# Stepper_driver_group.net
KiCad netlist of a schematic drawn in Altium Designer
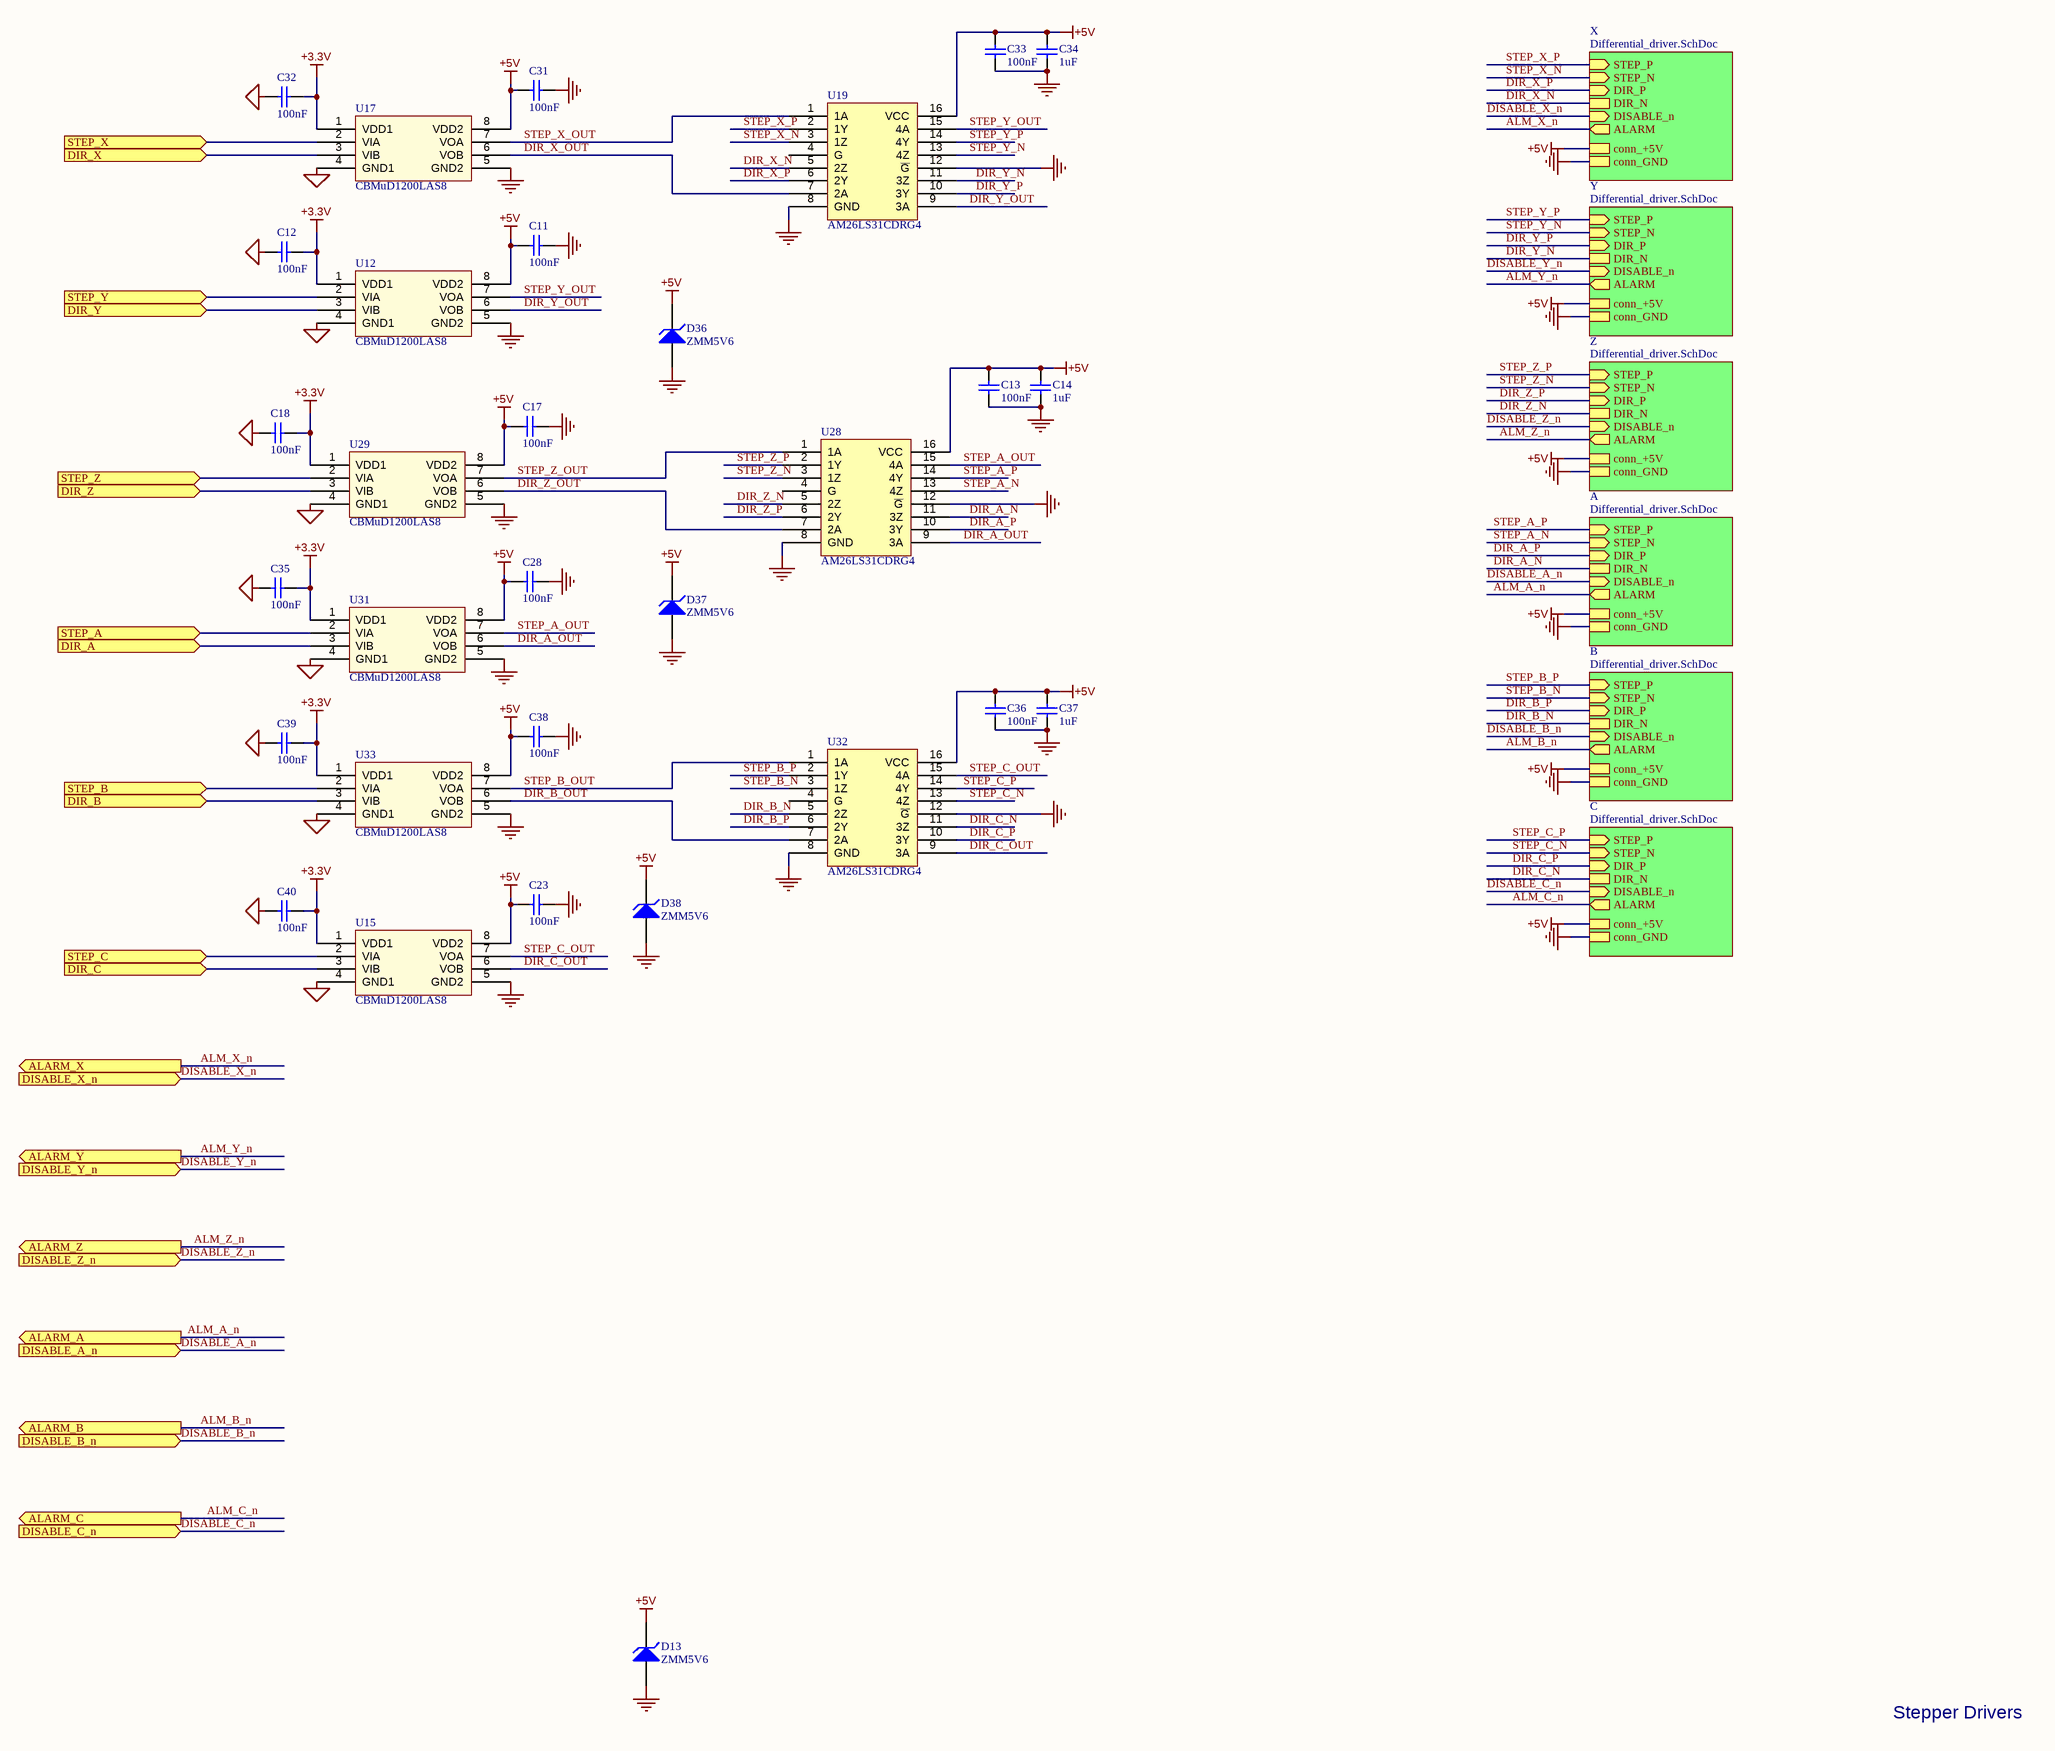
[diagram p0: Stepper_driver_group.SchDoc]

(export (version "E")
  (design (tool "Eeschema 10.0.6"))
  (components
    (comp (ref "C11")
      (value "100nF")
      (footprint "0402_C")
      (description "Chip capacitors")
      (fields
        (field (name "MANUFACTURER") "Samsung Electro-Mechanics")
        (field (name "PARTNUMBER") "CL05B104KO5NNNC")
      )
      (libsource (lib "Cap") (part "0402 100nF (104) 10% 16V"))
    )
    (comp (ref "C12")
      (value "100nF")
      (footprint "0402_C")
      (description "Chip capacitors")
      (fields
        (field (name "MANUFACTURER") "Samsung Electro-Mechanics")
        (field (name "PARTNUMBER") "CL05B104KO5NNNC")
      )
      (libsource (lib "Cap") (part "0402 100nF (104) 10% 16V"))
    )
    (comp (ref "C13")
      (value "100nF")
      (footprint "0402_C")
      (description "Chip capacitors")
      (fields
        (field (name "MANUFACTURER") "Samsung Electro-Mechanics")
        (field (name "PARTNUMBER") "CL05B104KO5NNNC")
      )
      (libsource (lib "Cap") (part "0402 100nF (104) 10% 16V"))
    )
    (comp (ref "C14")
      (value "1uF")
      (footprint "0603_C")
      (description "Chip capacitors")
      (fields
        (field (name "MANUFACTURER") "Samsung Electro-Mechanics")
        (field (name "PARTNUMBER") "CL10A105KB8NNNC")
      )
      (libsource (lib "Cap") (part "0603 1uF (105) 10% 50V"))
    )
    (comp (ref "C17")
      (value "100nF")
      (footprint "0402_C")
      (description "Chip capacitors")
      (fields
        (field (name "MANUFACTURER") "Samsung Electro-Mechanics")
        (field (name "PARTNUMBER") "CL05B104KO5NNNC")
      )
      (libsource (lib "Cap") (part "0402 100nF (104) 10% 16V"))
    )
    (comp (ref "C18")
      (value "100nF")
      (footprint "0402_C")
      (description "Chip capacitors")
      (fields
        (field (name "MANUFACTURER") "Samsung Electro-Mechanics")
        (field (name "PARTNUMBER") "CL05B104KO5NNNC")
      )
      (libsource (lib "Cap") (part "0402 100nF (104) 10% 16V"))
    )
    (comp (ref "C23")
      (value "100nF")
      (footprint "0402_C")
      (description "Chip capacitors")
      (fields
        (field (name "MANUFACTURER") "Samsung Electro-Mechanics")
        (field (name "PARTNUMBER") "CL05B104KO5NNNC")
      )
      (libsource (lib "Cap") (part "0402 100nF (104) 10% 16V"))
    )
    (comp (ref "C28")
      (value "100nF")
      (footprint "0402_C")
      (description "Chip capacitors")
      (fields
        (field (name "MANUFACTURER") "Samsung Electro-Mechanics")
        (field (name "PARTNUMBER") "CL05B104KO5NNNC")
      )
      (libsource (lib "Cap") (part "0402 100nF (104) 10% 16V"))
    )
    (comp (ref "C31")
      (value "100nF")
      (footprint "0402_C")
      (description "Chip capacitors")
      (fields
        (field (name "MANUFACTURER") "Samsung Electro-Mechanics")
        (field (name "PARTNUMBER") "CL05B104KO5NNNC")
      )
      (libsource (lib "Cap") (part "0402 100nF (104) 10% 16V"))
    )
    (comp (ref "C32")
      (value "100nF")
      (footprint "0402_C")
      (description "Chip capacitors")
      (fields
        (field (name "MANUFACTURER") "Samsung Electro-Mechanics")
        (field (name "PARTNUMBER") "CL05B104KO5NNNC")
      )
      (libsource (lib "Cap") (part "0402 100nF (104) 10% 16V"))
    )
    (comp (ref "C33")
      (value "100nF")
      (footprint "0402_C")
      (description "Chip capacitors")
      (fields
        (field (name "MANUFACTURER") "Samsung Electro-Mechanics")
        (field (name "PARTNUMBER") "CL05B104KO5NNNC")
      )
      (libsource (lib "Cap") (part "0402 100nF (104) 10% 16V"))
    )
    (comp (ref "C34")
      (value "1uF")
      (footprint "0603_C")
      (description "Chip capacitors")
      (fields
        (field (name "MANUFACTURER") "Samsung Electro-Mechanics")
        (field (name "PARTNUMBER") "CL10A105KB8NNNC")
      )
      (libsource (lib "Cap") (part "0603 1uF (105) 10% 50V"))
    )
    (comp (ref "C35")
      (value "100nF")
      (footprint "0402_C")
      (description "Chip capacitors")
      (fields
        (field (name "MANUFACTURER") "Samsung Electro-Mechanics")
        (field (name "PARTNUMBER") "CL05B104KO5NNNC")
      )
      (libsource (lib "Cap") (part "0402 100nF (104) 10% 16V"))
    )
    (comp (ref "C36")
      (value "100nF")
      (footprint "0402_C")
      (description "Chip capacitors")
      (fields
        (field (name "MANUFACTURER") "Samsung Electro-Mechanics")
        (field (name "PARTNUMBER") "CL05B104KO5NNNC")
      )
      (libsource (lib "Cap") (part "0402 100nF (104) 10% 16V"))
    )
    (comp (ref "C37")
      (value "1uF")
      (footprint "0603_C")
      (description "Chip capacitors")
      (fields
        (field (name "MANUFACTURER") "Samsung Electro-Mechanics")
        (field (name "PARTNUMBER") "CL10A105KB8NNNC")
      )
      (libsource (lib "Cap") (part "0603 1uF (105) 10% 50V"))
    )
    (comp (ref "C38")
      (value "100nF")
      (footprint "0402_C")
      (description "Chip capacitors")
      (fields
        (field (name "MANUFACTURER") "Samsung Electro-Mechanics")
        (field (name "PARTNUMBER") "CL05B104KO5NNNC")
      )
      (libsource (lib "Cap") (part "0402 100nF (104) 10% 16V"))
    )
    (comp (ref "C39")
      (value "100nF")
      (footprint "0402_C")
      (description "Chip capacitors")
      (fields
        (field (name "MANUFACTURER") "Samsung Electro-Mechanics")
        (field (name "PARTNUMBER") "CL05B104KO5NNNC")
      )
      (libsource (lib "Cap") (part "0402 100nF (104) 10% 16V"))
    )
    (comp (ref "C40")
      (value "100nF")
      (footprint "0402_C")
      (description "Chip capacitors")
      (fields
        (field (name "MANUFACTURER") "Samsung Electro-Mechanics")
        (field (name "PARTNUMBER") "CL05B104KO5NNNC")
      )
      (libsource (lib "Cap") (part "0402 100nF (104) 10% 16V"))
    )
    (comp (ref "D13")
      (value "ZMM5V6")
      (footprint "LL-34")
      (description "500mW - 0.1uA @ 1V 5.6V LL-34 Zener Diodes ROHS")
      (libsource (lib "Zener") (part "LL-34 ZMM5V6"))
    )
    (comp (ref "D36")
      (value "ZMM5V6")
      (footprint "LL-34")
      (description "500mW - 0.1uA @ 1V 5.6V LL-34 Zener Diodes ROHS")
      (libsource (lib "Zener") (part "LL-34 ZMM5V6"))
    )
    (comp (ref "D37")
      (value "ZMM5V6")
      (footprint "LL-34")
      (description "500mW - 0.1uA @ 1V 5.6V LL-34 Zener Diodes ROHS")
      (libsource (lib "Zener") (part "LL-34 ZMM5V6"))
    )
    (comp (ref "D38")
      (value "ZMM5V6")
      (footprint "LL-34")
      (description "500mW - 0.1uA @ 1V 5.6V LL-34 Zener Diodes ROHS")
      (libsource (lib "Zener") (part "LL-34 ZMM5V6"))
    )
    (comp (ref "U12")
      (value "CBMuD1200LAS8")
      (footprint "SOIC-8_150mil")
      (description "Dual Channel Isolator")
      (libsource (lib "IC") (part "CBMuD1200LAS8"))
    )
    (comp (ref "U15")
      (value "CBMuD1200LAS8")
      (footprint "SOIC-8_150mil")
      (description "Dual Channel Isolator")
      (libsource (lib "IC") (part "CBMuD1200LAS8"))
    )
    (comp (ref "U17")
      (value "CBMuD1200LAS8")
      (footprint "SOIC-8_150mil")
      (description "Dual Channel Isolator")
      (libsource (lib "IC") (part "CBMuD1200LAS8"))
    )
    (comp (ref "U19")
      (value "AM26LS31CDRG4")
      (footprint "SOIC-16_150mil")
      (description "4/0 Driver - RS422, RS485 16-SOIC")
      (libsource (lib "IC") (part "AM26LS31CDRG4_[C6179]"))
    )
    (comp (ref "U28")
      (value "AM26LS31CDRG4")
      (footprint "SOIC-16_150mil")
      (description "4/0 Driver - RS422, RS485 16-SOIC")
      (libsource (lib "IC") (part "AM26LS31CDRG4_[C6179]"))
    )
    (comp (ref "U29")
      (value "CBMuD1200LAS8")
      (footprint "SOIC-8_150mil")
      (description "Dual Channel Isolator")
      (libsource (lib "IC") (part "CBMuD1200LAS8"))
    )
    (comp (ref "U31")
      (value "CBMuD1200LAS8")
      (footprint "SOIC-8_150mil")
      (description "Dual Channel Isolator")
      (libsource (lib "IC") (part "CBMuD1200LAS8"))
    )
    (comp (ref "U32")
      (value "AM26LS31CDRG4")
      (footprint "SOIC-16_150mil")
      (description "4/0 Driver - RS422, RS485 16-SOIC")
      (libsource (lib "IC") (part "AM26LS31CDRG4_[C6179]"))
    )
    (comp (ref "U33")
      (value "CBMuD1200LAS8")
      (footprint "SOIC-8_150mil")
      (description "Dual Channel Isolator")
      (libsource (lib "IC") (part "CBMuD1200LAS8"))
    )
  )
  (nets
    (net (code "1") (name "+3.3V") (class "Default")
      (node (ref "C12") (pin "1") (pinfunction "1_1") (pintype "passive"))
      (node (ref "C18") (pin "1") (pinfunction "1_1") (pintype "passive"))
      (node (ref "C32") (pin "1") (pinfunction "1_1") (pintype "passive"))
      (node (ref "C35") (pin "1") (pinfunction "1_1") (pintype "passive"))
      (node (ref "C39") (pin "1") (pinfunction "1_1") (pintype "passive"))
      (node (ref "C40") (pin "1") (pinfunction "1_1") (pintype "passive"))
      (node (ref "U12") (pin "1") (pinfunction "VDD1_1") (pintype "passive"))
      (node (ref "U15") (pin "1") (pinfunction "VDD1_1") (pintype "passive"))
      (node (ref "U17") (pin "1") (pinfunction "VDD1_1") (pintype "passive"))
      (node (ref "U29") (pin "1") (pinfunction "VDD1_1") (pintype "passive"))
      (node (ref "U31") (pin "1") (pinfunction "VDD1_1") (pintype "passive"))
      (node (ref "U33") (pin "1") (pinfunction "VDD1_1") (pintype "passive"))
    )
    (net (code "2") (name "+5V") (class "Default")
      (node (ref "C11") (pin "2") (pinfunction "2_2") (pintype "passive"))
      (node (ref "C13") (pin "1") (pinfunction "1_1") (pintype "passive"))
      (node (ref "C14") (pin "1") (pinfunction "1_1") (pintype "passive"))
      (node (ref "C17") (pin "2") (pinfunction "2_2") (pintype "passive"))
      (node (ref "C23") (pin "2") (pinfunction "2_2") (pintype "passive"))
      (node (ref "C28") (pin "2") (pinfunction "2_2") (pintype "passive"))
      (node (ref "C31") (pin "2") (pinfunction "2_2") (pintype "passive"))
      (node (ref "C33") (pin "1") (pinfunction "1_1") (pintype "passive"))
      (node (ref "C34") (pin "1") (pinfunction "1_1") (pintype "passive"))
      (node (ref "C36") (pin "1") (pinfunction "1_1") (pintype "passive"))
      (node (ref "C37") (pin "1") (pinfunction "1_1") (pintype "passive"))
      (node (ref "C38") (pin "2") (pinfunction "2_2") (pintype "passive"))
      (node (ref "D13") (pin "2") (pinfunction "K_2") (pintype "passive"))
      (node (ref "D36") (pin "2") (pinfunction "K_2") (pintype "passive"))
      (node (ref "D37") (pin "2") (pinfunction "K_2") (pintype "passive"))
      (node (ref "D38") (pin "2") (pinfunction "K_2") (pintype "passive"))
      (node (ref "U12") (pin "8") (pinfunction "VDD2_8") (pintype "passive"))
      (node (ref "U15") (pin "8") (pinfunction "VDD2_8") (pintype "passive"))
      (node (ref "U17") (pin "8") (pinfunction "VDD2_8") (pintype "passive"))
      (node (ref "U19") (pin "16") (pinfunction "VCC_16") (pintype "passive"))
      (node (ref "U28") (pin "16") (pinfunction "VCC_16") (pintype "passive"))
      (node (ref "U29") (pin "8") (pinfunction "VDD2_8") (pintype "passive"))
      (node (ref "U31") (pin "8") (pinfunction "VDD2_8") (pintype "passive"))
      (node (ref "U32") (pin "16") (pinfunction "VCC_16") (pintype "passive"))
      (node (ref "U33") (pin "8") (pinfunction "VDD2_8") (pintype "passive"))
    )
    (net (code "9") (name "/DIR_A") (class "Default")
      (node (ref "U31") (pin "3") (pinfunction "VIB_3") (pintype "passive"))
    )
    (net (code "10") (name "/DIR_A_N") (class "Default")
      (node (ref "U28") (pin "11") (pinfunction "3Z_11") (pintype "passive"))
    )
    (net (code "11") (name "/DIR_A_OUT") (class "Default")
      (node (ref "U28") (pin "9") (pinfunction "3A_9") (pintype "passive"))
      (node (ref "U31") (pin "6") (pinfunction "VOB_6") (pintype "passive"))
    )
    (net (code "12") (name "/DIR_A_P") (class "Default")
      (node (ref "U28") (pin "10") (pinfunction "3Y_10") (pintype "passive"))
    )
    (net (code "13") (name "/DIR_B") (class "Default")
      (node (ref "U33") (pin "3") (pinfunction "VIB_3") (pintype "passive"))
    )
    (net (code "14") (name "/DIR_B_N") (class "Default")
      (node (ref "U32") (pin "5") (pinfunction "2Z_5") (pintype "passive"))
    )
    (net (code "15") (name "/DIR_B_OUT") (class "Default")
      (node (ref "U32") (pin "7") (pinfunction "2A_7") (pintype "passive"))
      (node (ref "U33") (pin "6") (pinfunction "VOB_6") (pintype "passive"))
    )
    (net (code "16") (name "/DIR_B_P") (class "Default")
      (node (ref "U32") (pin "6") (pinfunction "2Y_6") (pintype "passive"))
    )
    (net (code "17") (name "/DIR_C") (class "Default")
      (node (ref "U15") (pin "3") (pinfunction "VIB_3") (pintype "passive"))
    )
    (net (code "18") (name "/DIR_C_N") (class "Default")
      (node (ref "U32") (pin "11") (pinfunction "3Z_11") (pintype "passive"))
    )
    (net (code "19") (name "/DIR_C_OUT") (class "Default")
      (node (ref "U15") (pin "6") (pinfunction "VOB_6") (pintype "passive"))
      (node (ref "U32") (pin "9") (pinfunction "3A_9") (pintype "passive"))
    )
    (net (code "20") (name "/DIR_C_P") (class "Default")
      (node (ref "U32") (pin "10") (pinfunction "3Y_10") (pintype "passive"))
    )
    (net (code "21") (name "/DIR_X") (class "Default")
      (node (ref "U17") (pin "3") (pinfunction "VIB_3") (pintype "passive"))
    )
    (net (code "22") (name "/DIR_X_N") (class "Default")
      (node (ref "U19") (pin "5") (pinfunction "2Z_5") (pintype "passive"))
    )
    (net (code "23") (name "/DIR_X_OUT") (class "Default")
      (node (ref "U17") (pin "6") (pinfunction "VOB_6") (pintype "passive"))
      (node (ref "U19") (pin "7") (pinfunction "2A_7") (pintype "passive"))
    )
    (net (code "24") (name "/DIR_X_P") (class "Default")
      (node (ref "U19") (pin "6") (pinfunction "2Y_6") (pintype "passive"))
    )
    (net (code "25") (name "/DIR_Y") (class "Default")
      (node (ref "U12") (pin "3") (pinfunction "VIB_3") (pintype "passive"))
    )
    (net (code "26") (name "/DIR_Y_N") (class "Default")
      (node (ref "U19") (pin "11") (pinfunction "3Z_11") (pintype "passive"))
    )
    (net (code "27") (name "/DIR_Y_OUT") (class "Default")
      (node (ref "U12") (pin "6") (pinfunction "VOB_6") (pintype "passive"))
      (node (ref "U19") (pin "9") (pinfunction "3A_9") (pintype "passive"))
    )
    (net (code "28") (name "/DIR_Y_P") (class "Default")
      (node (ref "U19") (pin "10") (pinfunction "3Y_10") (pintype "passive"))
    )
    (net (code "29") (name "/DIR_Z") (class "Default")
      (node (ref "U29") (pin "3") (pinfunction "VIB_3") (pintype "passive"))
    )
    (net (code "30") (name "/DIR_Z_N") (class "Default")
      (node (ref "U28") (pin "5") (pinfunction "2Z_5") (pintype "passive"))
    )
    (net (code "31") (name "/DIR_Z_OUT") (class "Default")
      (node (ref "U28") (pin "7") (pinfunction "2A_7") (pintype "passive"))
      (node (ref "U29") (pin "6") (pinfunction "VOB_6") (pintype "passive"))
    )
    (net (code "32") (name "/DIR_Z_P") (class "Default")
      (node (ref "U28") (pin "6") (pinfunction "2Y_6") (pintype "passive"))
    )
    (net (code "39") (name "/STEP_A") (class "Default")
      (node (ref "U31") (pin "2") (pinfunction "VIA_2") (pintype "passive"))
    )
    (net (code "40") (name "/STEP_A_N") (class "Default")
      (node (ref "U28") (pin "13") (pinfunction "4Z_13") (pintype "passive"))
    )
    (net (code "41") (name "/STEP_A_OUT") (class "Default")
      (node (ref "U28") (pin "15") (pinfunction "4A_15") (pintype "passive"))
      (node (ref "U31") (pin "7") (pinfunction "VOA_7") (pintype "passive"))
    )
    (net (code "42") (name "/STEP_A_P") (class "Default")
      (node (ref "U28") (pin "14") (pinfunction "4Y_14") (pintype "passive"))
    )
    (net (code "43") (name "/STEP_B") (class "Default")
      (node (ref "U33") (pin "2") (pinfunction "VIA_2") (pintype "passive"))
    )
    (net (code "44") (name "/STEP_B_N") (class "Default")
      (node (ref "U32") (pin "3") (pinfunction "1Z_3") (pintype "passive"))
    )
    (net (code "45") (name "/STEP_B_OUT") (class "Default")
      (node (ref "U32") (pin "1") (pinfunction "1A_1") (pintype "passive"))
      (node (ref "U33") (pin "7") (pinfunction "VOA_7") (pintype "passive"))
    )
    (net (code "46") (name "/STEP_B_P") (class "Default")
      (node (ref "U32") (pin "2") (pinfunction "1Y_2") (pintype "passive"))
    )
    (net (code "47") (name "/STEP_C") (class "Default")
      (node (ref "U15") (pin "2") (pinfunction "VIA_2") (pintype "passive"))
    )
    (net (code "48") (name "/STEP_C_N") (class "Default")
      (node (ref "U32") (pin "13") (pinfunction "4Z_13") (pintype "passive"))
    )
    (net (code "49") (name "/STEP_C_OUT") (class "Default")
      (node (ref "U15") (pin "7") (pinfunction "VOA_7") (pintype "passive"))
      (node (ref "U32") (pin "15") (pinfunction "4A_15") (pintype "passive"))
    )
    (net (code "50") (name "/STEP_C_P") (class "Default")
      (node (ref "U32") (pin "14") (pinfunction "4Y_14") (pintype "passive"))
    )
    (net (code "51") (name "/STEP_X") (class "Default")
      (node (ref "U17") (pin "2") (pinfunction "VIA_2") (pintype "passive"))
    )
    (net (code "52") (name "/STEP_X_N") (class "Default")
      (node (ref "U19") (pin "3") (pinfunction "1Z_3") (pintype "passive"))
    )
    (net (code "53") (name "/STEP_X_OUT") (class "Default")
      (node (ref "U17") (pin "7") (pinfunction "VOA_7") (pintype "passive"))
      (node (ref "U19") (pin "1") (pinfunction "1A_1") (pintype "passive"))
    )
    (net (code "54") (name "/STEP_X_P") (class "Default")
      (node (ref "U19") (pin "2") (pinfunction "1Y_2") (pintype "passive"))
    )
    (net (code "55") (name "/STEP_Y") (class "Default")
      (node (ref "U12") (pin "2") (pinfunction "VIA_2") (pintype "passive"))
    )
    (net (code "56") (name "/STEP_Y_N") (class "Default")
      (node (ref "U19") (pin "13") (pinfunction "4Z_13") (pintype "passive"))
    )
    (net (code "57") (name "/STEP_Y_OUT") (class "Default")
      (node (ref "U12") (pin "7") (pinfunction "VOA_7") (pintype "passive"))
      (node (ref "U19") (pin "15") (pinfunction "4A_15") (pintype "passive"))
    )
    (net (code "58") (name "/STEP_Y_P") (class "Default")
      (node (ref "U19") (pin "14") (pinfunction "4Y_14") (pintype "passive"))
    )
    (net (code "59") (name "/STEP_Z") (class "Default")
      (node (ref "U29") (pin "2") (pinfunction "VIA_2") (pintype "passive"))
    )
    (net (code "60") (name "/STEP_Z_N") (class "Default")
      (node (ref "U28") (pin "3") (pinfunction "1Z_3") (pintype "passive"))
    )
    (net (code "61") (name "/STEP_Z_OUT") (class "Default")
      (node (ref "U28") (pin "1") (pinfunction "1A_1") (pintype "passive"))
      (node (ref "U29") (pin "7") (pinfunction "VOA_7") (pintype "passive"))
    )
    (net (code "62") (name "/STEP_Z_P") (class "Default")
      (node (ref "U28") (pin "2") (pinfunction "1Y_2") (pintype "passive"))
    )
    (net (code "63") (name "GND") (class "Default")
      (node (ref "C11") (pin "1") (pinfunction "1_1") (pintype "passive"))
      (node (ref "C13") (pin "2") (pinfunction "2_2") (pintype "passive"))
      (node (ref "C14") (pin "2") (pinfunction "2_2") (pintype "passive"))
      (node (ref "C17") (pin "1") (pinfunction "1_1") (pintype "passive"))
      (node (ref "C23") (pin "1") (pinfunction "1_1") (pintype "passive"))
      (node (ref "C28") (pin "1") (pinfunction "1_1") (pintype "passive"))
      (node (ref "C31") (pin "1") (pinfunction "1_1") (pintype "passive"))
      (node (ref "C33") (pin "2") (pinfunction "2_2") (pintype "passive"))
      (node (ref "C34") (pin "2") (pinfunction "2_2") (pintype "passive"))
      (node (ref "C36") (pin "2") (pinfunction "2_2") (pintype "passive"))
      (node (ref "C37") (pin "2") (pinfunction "2_2") (pintype "passive"))
      (node (ref "C38") (pin "1") (pinfunction "1_1") (pintype "passive"))
      (node (ref "D13") (pin "1") (pinfunction "A_1") (pintype "passive"))
      (node (ref "D36") (pin "1") (pinfunction "A_1") (pintype "passive"))
      (node (ref "D37") (pin "1") (pinfunction "A_1") (pintype "passive"))
      (node (ref "D38") (pin "1") (pinfunction "A_1") (pintype "passive"))
      (node (ref "U12") (pin "5") (pinfunction "GND2_5") (pintype "passive"))
      (node (ref "U15") (pin "5") (pinfunction "GND2_5") (pintype "passive"))
      (node (ref "U17") (pin "5") (pinfunction "GND2_5") (pintype "passive"))
      (node (ref "U19") (pin "12") (pinfunction "~{G}_12") (pintype "passive"))
      (node (ref "U19") (pin "8") (pinfunction "GND_8") (pintype "passive"))
      (node (ref "U28") (pin "12") (pinfunction "~{G}_12") (pintype "passive"))
      (node (ref "U28") (pin "8") (pinfunction "GND_8") (pintype "passive"))
      (node (ref "U29") (pin "5") (pinfunction "GND2_5") (pintype "passive"))
      (node (ref "U31") (pin "5") (pinfunction "GND2_5") (pintype "passive"))
      (node (ref "U32") (pin "12") (pinfunction "~{G}_12") (pintype "passive"))
      (node (ref "U32") (pin "8") (pinfunction "GND_8") (pintype "passive"))
      (node (ref "U33") (pin "5") (pinfunction "GND2_5") (pintype "passive"))
    )
    (net (code "64") (name "MCU_GND") (class "Default")
      (node (ref "C12") (pin "2") (pinfunction "2_2") (pintype "passive"))
      (node (ref "C18") (pin "2") (pinfunction "2_2") (pintype "passive"))
      (node (ref "C32") (pin "2") (pinfunction "2_2") (pintype "passive"))
      (node (ref "C35") (pin "2") (pinfunction "2_2") (pintype "passive"))
      (node (ref "C39") (pin "2") (pinfunction "2_2") (pintype "passive"))
      (node (ref "C40") (pin "2") (pinfunction "2_2") (pintype "passive"))
      (node (ref "U12") (pin "4") (pinfunction "GND1_4") (pintype "passive"))
      (node (ref "U15") (pin "4") (pinfunction "GND1_4") (pintype "passive"))
      (node (ref "U17") (pin "4") (pinfunction "GND1_4") (pintype "passive"))
      (node (ref "U29") (pin "4") (pinfunction "GND1_4") (pintype "passive"))
      (node (ref "U31") (pin "4") (pinfunction "GND1_4") (pintype "passive"))
      (node (ref "U33") (pin "4") (pinfunction "GND1_4") (pintype "passive"))
    )
    (net (code "65") (name "unconnected-(U19-G-Pad4)") (class "Default")
      (node (ref "U19") (pin "4") (pinfunction "G_4") (pintype "passive"))
    )
    (net (code "66") (name "unconnected-(U28-G-Pad4)") (class "Default")
      (node (ref "U28") (pin "4") (pinfunction "G_4") (pintype "passive"))
    )
    (net (code "67") (name "unconnected-(U32-G-Pad4)") (class "Default")
      (node (ref "U32") (pin "4") (pinfunction "G_4") (pintype "passive"))
    )
  )
)
